# Interface.net
KiCad netlist of a schematic drawn in Altium Designer
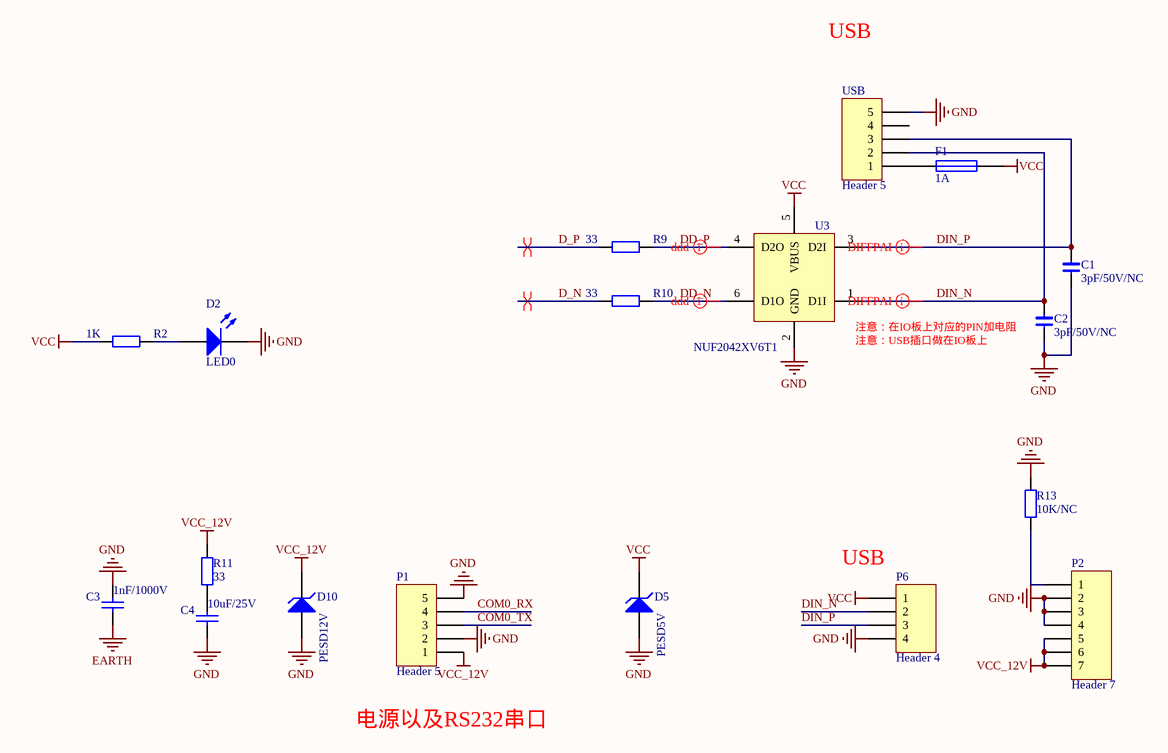
[diagram p0: Interface.SchDoc]

(export (version "E")
  (design (tool "Eeschema 10.0.6"))
  (components
    (comp (ref "C1")
      (value "3pF/50V/NC")
      (footprint "0402C")
      (description "C")
      (libsource (lib "Top") (part "C"))
    )
    (comp (ref "C2")
      (value "3pF/50V/NC")
      (footprint "0402C")
      (description "C")
      (libsource (lib "Top") (part "C"))
    )
    (comp (ref "C3")
      (value "1nF/1000V")
      (footprint "1206C")
      (description "Capacitor")
      (fields (field (name "PUBLISHER") "Altium Limited"))
      (libsource (lib "Miscellaneous Devices") (part "Cap"))
    )
    (comp (ref "C4")
      (value "10uF/25V")
      (footprint "0603C")
      (description "Capacitor")
      (fields (field (name "PUBLISHER") "Altium Limited"))
      (libsource (lib "Miscellaneous Devices") (part "Cap"))
    )
    (comp (ref "D2")
      (value "LED0")
      (footprint "0603LED")
      (description "Typical INFRARED GaAs LED")
      (fields (field (name "PUBLISHER") "Altium Limited"))
      (libsource (lib "Miscellaneous Devices") (part "LED0"))
    )
    (comp (ref "D5")
      (value "PESD5V")
      (footprint "SOD323")
      (description "Zener Diode")
      (fields (field (name "PUBLISHER") "Altium Limited"))
      (libsource (lib "Miscellaneous Devices") (part "D Zener"))
    )
    (comp (ref "D10")
      (value "PESD12V")
      (footprint "SOD323")
      (description "Zener Diode")
      (fields (field (name "PUBLISHER") "Altium Limited"))
      (libsource (lib "Miscellaneous Devices") (part "D Zener"))
    )
    (comp (ref "F1")
      (value "1A")
      (footprint "0805R")
      (description "Fuse")
      (fields (field (name "PUBLISHER") "Altium Limited"))
      (libsource (lib "Miscellaneous Devices") (part "Fuse 1"))
    )
    (comp (ref "P1")
      (value "Header 5")
      (footprint "KF350-5P")
      (description "Header, 5-Pin")
      (fields (field (name "PUBLISHER") "Altium Limited"))
      (libsource (lib "Miscellaneous Connectors") (part "Header 5"))
    )
    (comp (ref "P2")
      (value "Header 7")
      (footprint "7×1.25mmSMT")
      (description "Header, 7-Pin")
      (fields (field (name "PUBLISHER") "Altium Limited"))
      (libsource (lib "Miscellaneous Connectors") (part "Header 7"))
    )
    (comp (ref "P6")
      (value "Header 4")
      (footprint "4×1.25mmSMT")
      (description "Header, 4-Pin")
      (fields (field (name "PUBLISHER") "Altium Limited"))
      (libsource (lib "Miscellaneous Connectors") (part "Header 4"))
    )
    (comp (ref "R2")
      (value "1K")
      (footprint "0402R")
      (description "Resistor SMD - IEC symbol version")
      (libsource (lib "SX1276_e266v02a") (part "Resistor"))
    )
    (comp (ref "R9")
      (value "33")
      (footprint "0402R")
      (description "Resistor SMD - IEC symbol version")
      (libsource (lib "SX1276_e266v02a") (part "Resistor"))
    )
    (comp (ref "R10")
      (value "33")
      (footprint "0402R")
      (description "Resistor SMD - IEC symbol version")
      (libsource (lib "SX1276_e266v02a") (part "Resistor"))
    )
    (comp (ref "R11")
      (value "33")
      (footprint "0402R")
      (description "Resistor SMD - IEC symbol version")
      (libsource (lib "") (part "Resistor_1"))
    )
    (comp (ref "R13")
      (value "10K/NC")
      (footprint "0402R")
      (description "Resistor SMD - IEC symbol version")
      (libsource (lib "") (part "Resistor_2"))
    )
    (comp (ref "U3")
      (value "NUF2042XV6T1")
      (footprint "SOT563-6")
      (libsource (lib "Myself_1") (part "NUF2042XV6T1"))
    )
    (comp (ref "USB")
      (value "Header 5")
      (footprint "Micro_USB_PH")
      (description "Header, 5-Pin")
      (fields (field (name "PUBLISHER") "Altium Limited"))
      (libsource (lib "Miscellaneous Connectors") (part "Header 5"))
    )
  )
  (nets
    (net (code "1") (name "/COM0_RX") (class "Default")
      (node (ref "P1") (pin "4") (pinfunction "4_4") (pintype "passive"))
    )
    (net (code "2") (name "/COM0_TX") (class "Default")
      (node (ref "P1") (pin "3") (pinfunction "3_3") (pintype "passive"))
    )
    (net (code "3") (name "/DD_N") (class "Default")
      (node (ref "R10") (pin "2") (pinfunction "2_2") (pintype "passive"))
      (node (ref "U3") (pin "6") (pinfunction "D1O_6") (pintype "passive"))
    )
    (net (code "4") (name "/DD_P") (class "Default")
      (node (ref "R9") (pin "2") (pinfunction "2_2") (pintype "passive"))
      (node (ref "U3") (pin "4") (pinfunction "D2O_4") (pintype "passive"))
    )
    (net (code "5") (name "/DIN_N") (class "Default")
      (node (ref "C2") (pin "1") (pintype "passive"))
      (node (ref "P6") (pin "2") (pinfunction "2_2") (pintype "passive"))
      (node (ref "U3") (pin "1") (pinfunction "D1I_1") (pintype "passive"))
      (node (ref "USB") (pin "2") (pinfunction "2_2") (pintype "passive"))
    )
    (net (code "6") (name "/DIN_P") (class "Default")
      (node (ref "C1") (pin "1") (pintype "passive"))
      (node (ref "P6") (pin "3") (pinfunction "3_3") (pintype "passive"))
      (node (ref "U3") (pin "3") (pinfunction "D2I_3") (pintype "passive"))
      (node (ref "USB") (pin "3") (pinfunction "3_3") (pintype "passive"))
    )
    (net (code "7") (name "/D_N") (class "Default")
      (node (ref "R10") (pin "1") (pinfunction "1_1") (pintype "passive"))
    )
    (net (code "8") (name "/D_P") (class "Default")
      (node (ref "R9") (pin "1") (pinfunction "1_1") (pintype "passive"))
    )
    (net (code "9") (name "EARTH") (class "Default")
      (node (ref "C3") (pin "1") (pinfunction "1_1") (pintype "passive"))
    )
    (net (code "10") (name "GND") (class "Default")
      (node (ref "C1") (pin "2") (pintype "passive"))
      (node (ref "C2") (pin "2") (pintype "passive"))
      (node (ref "C3") (pin "2") (pinfunction "2_2") (pintype "passive"))
      (node (ref "C4") (pin "1") (pinfunction "1_1") (pintype "passive"))
      (node (ref "D10") (pin "A") (pinfunction "A_A") (pintype "passive"))
      (node (ref "D2") (pin "2") (pinfunction "K_2") (pintype "passive"))
      (node (ref "D5") (pin "A") (pinfunction "A_A") (pintype "passive"))
      (node (ref "P1") (pin "2") (pinfunction "2_2") (pintype "passive"))
      (node (ref "P1") (pin "5") (pinfunction "5_5") (pintype "passive"))
      (node (ref "P2") (pin "2") (pinfunction "2_2") (pintype "passive"))
      (node (ref "P2") (pin "3") (pinfunction "3_3") (pintype "passive"))
      (node (ref "P2") (pin "4") (pinfunction "4_4") (pintype "passive"))
      (node (ref "P6") (pin "4") (pinfunction "4_4") (pintype "passive"))
      (node (ref "R13") (pin "1") (pinfunction "1_1") (pintype "passive"))
      (node (ref "U3") (pin "2") (pinfunction "GND_2") (pintype "passive"))
      (node (ref "USB") (pin "5") (pinfunction "5_5") (pintype "passive"))
    )
    (net (code "11") (name "Net-(C4-Pad2)") (class "Default")
      (node (ref "C4") (pin "2") (pinfunction "2_2") (pintype "passive"))
      (node (ref "R11") (pin "1") (pinfunction "1_1") (pintype "passive"))
    )
    (net (code "12") (name "Net-(D2-A)") (class "Default")
      (node (ref "D2") (pin "1") (pinfunction "A_1") (pintype "passive"))
      (node (ref "R2") (pin "2") (pinfunction "2_2") (pintype "passive"))
    )
    (net (code "13") (name "Net-(F1-Pad1)") (class "Default")
      (node (ref "F1") (pin "1") (pinfunction "1_1") (pintype "passive"))
      (node (ref "USB") (pin "1") (pinfunction "1_1") (pintype "passive"))
    )
    (net (code "14") (name "Net-(P2-Pad1)") (class "Default")
      (node (ref "P2") (pin "1") (pinfunction "1_1") (pintype "passive"))
      (node (ref "R13") (pin "2") (pinfunction "2_2") (pintype "passive"))
    )
    (net (code "15") (name "VCC") (class "Default")
      (node (ref "D5") (pin "K") (pinfunction "K_K") (pintype "passive"))
      (node (ref "F1") (pin "2") (pinfunction "2_2") (pintype "passive"))
      (node (ref "P6") (pin "1") (pinfunction "1_1") (pintype "passive"))
      (node (ref "R2") (pin "1") (pinfunction "1_1") (pintype "passive"))
      (node (ref "U3") (pin "5") (pinfunction "VBUS_5") (pintype "passive"))
    )
    (net (code "16") (name "VCC_12V") (class "Default")
      (node (ref "D10") (pin "K") (pinfunction "K_K") (pintype "passive"))
      (node (ref "P1") (pin "1") (pinfunction "1_1") (pintype "passive"))
      (node (ref "P2") (pin "5") (pinfunction "5_5") (pintype "passive"))
      (node (ref "P2") (pin "6") (pinfunction "6_6") (pintype "passive"))
      (node (ref "P2") (pin "7") (pinfunction "7_7") (pintype "passive"))
      (node (ref "R11") (pin "2") (pinfunction "2_2") (pintype "passive"))
    )
    (net (code "17") (name "unconnected-(USB-Pad4)") (class "Default")
      (node (ref "USB") (pin "4") (pinfunction "4_4") (pintype "passive"))
    )
  )
)
